# ArduinoUnoQ.net
KiCad netlist of a schematic drawn in Altium Designer
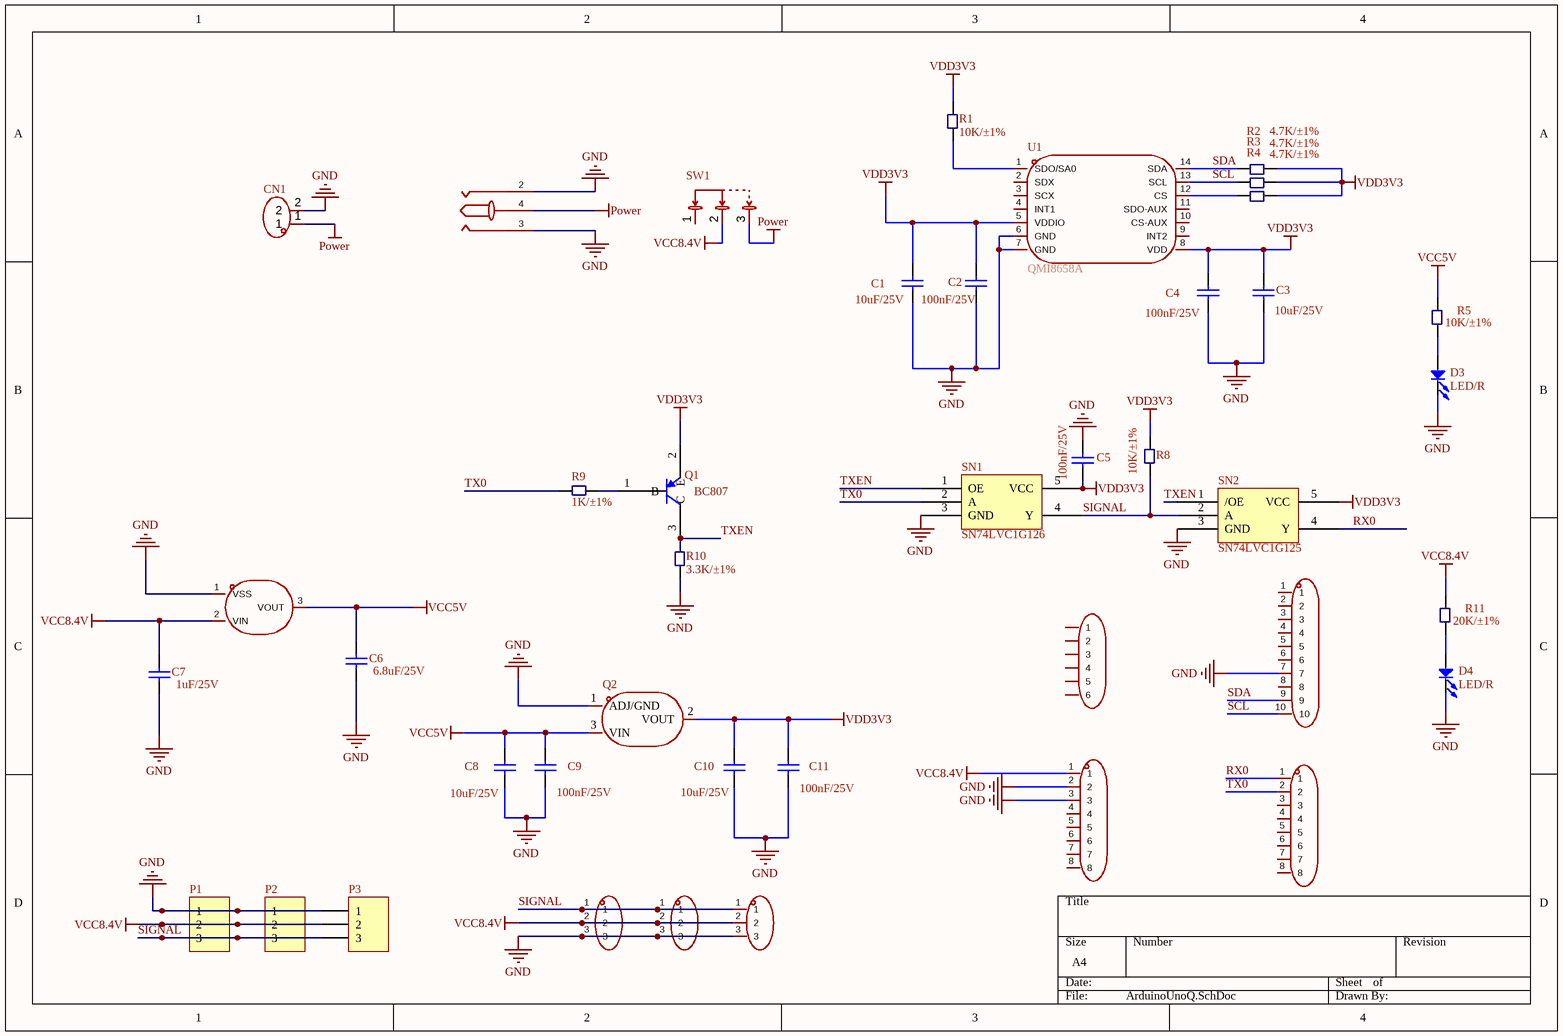
[diagram p0: ArduinoUnoQ.SchDoc]

(export (version "E")
  (design (tool "Eeschema 10.0.6"))
  (components
    (comp (ref "C1")
      (value "10uF/25V")
      (footprint "C0603")
      (description "0603贴片电容，±10%，50V")
      (fields (field (name "PUBLISHER") "Altium Limited"))
      (libsource (lib "ArduinoUnoQ") (part "0603 C"))
    )
    (comp (ref "C2")
      (value "100nF/25V")
      (footprint "C0603")
      (description "0603贴片电容，±10%，50V")
      (fields (field (name "PUBLISHER") "Altium Limited"))
      (libsource (lib "ArduinoUnoQ") (part "0603 C"))
    )
    (comp (ref "C3")
      (value "10uF/25V")
      (footprint "C0603")
      (description "0603贴片电容，±10%，50V")
      (fields (field (name "PUBLISHER") "Altium Limited"))
      (libsource (lib "ArduinoUnoQ") (part "0603 C"))
    )
    (comp (ref "C4")
      (value "100nF/25V")
      (footprint "C0603")
      (description "0603贴片电容，±10%，50V")
      (fields (field (name "PUBLISHER") "Altium Limited"))
      (libsource (lib "ArduinoUnoQ") (part "0603 C"))
    )
    (comp (ref "C5")
      (value "100nF/25V")
      (footprint "C0603")
      (description "0603贴片电容，±10%，50V")
      (libsource (lib "Cap") (part "0603 10nF (103) 10% 50V"))
    )
    (comp (ref "C6")
      (value "6.8uF/25V")
      (footprint "C0603")
      (description "0603贴片电容，±10%，50V")
      (fields (field (name "PUBLISHER") "Altium Limited"))
      (libsource (lib "ArduinoUnoQ") (part "0603 C"))
    )
    (comp (ref "C7")
      (value "1uF/25V")
      (footprint "C0603")
      (description "0603贴片电容，±10%，50V")
      (fields (field (name "PUBLISHER") "Altium Limited"))
      (libsource (lib "ArduinoUnoQ") (part "0603 C"))
    )
    (comp (ref "C8")
      (value "10uF/25V")
      (footprint "C0603")
      (description "0603贴片电容，±10%，50V")
      (fields (field (name "PUBLISHER") "Altium Limited"))
      (libsource (lib "ArduinoUnoQ") (part "0603 C"))
    )
    (comp (ref "C9")
      (value "100nF/25V")
      (footprint "C0603")
      (description "0603贴片电容，±10%，50V")
      (fields (field (name "PUBLISHER") "Altium Limited"))
      (libsource (lib "ArduinoUnoQ") (part "0603 C"))
    )
    (comp (ref "C10")
      (value "10uF/25V")
      (footprint "C0603")
      (description "0603贴片电容，±10%，50V")
      (fields (field (name "PUBLISHER") "Altium Limited"))
      (libsource (lib "ArduinoUnoQ") (part "0603 C"))
    )
    (comp (ref "C11")
      (value "100nF/25V")
      (footprint "C0603")
      (description "0603贴片电容，±10%，50V")
      (fields (field (name "PUBLISHER") "Altium Limited"))
      (libsource (lib "ArduinoUnoQ") (part "0603 C"))
    )
    (comp (ref "CN1")
      (value "ZX-XH2.54-2PWZ")
      (footprint "CONN-TH_2P-P2.50_ZX-XH2.54-2PWZ")
      (fields (field (name "MANUFACTURER") "Megastar(兆星)"))
      (libsource (lib "ArduinoUnoQ") (part "ZX-XH2.54-2PWZ"))
    )
    (comp (ref "D3")
      (value "LED/R")
      (footprint "D_SOD_523")
      (description "Typical INFRARED GaAs LED")
      (fields (field (name "PUBLISHER") "Altium Limited"))
      (libsource (lib "luwu") (part "LED"))
    )
    (comp (ref "D4")
      (value "LED/R")
      (footprint "D_SOD_523")
      (description "Typical INFRARED GaAs LED")
      (fields (field (name "PUBLISHER") "Altium Limited"))
      (libsource (lib "ArduinoUnoQ") (part "LED"))
    )
    (comp (ref "DC1")
      (value "kh-dc-007b-2.1g")
      (footprint "DC-IN-TH_KH-DC-007B-2.1G")
      (description "连接器类型:DC电源插座;安装方式:弯插;触点内径:-;触点外径:-;额定电流:3A;额定电压:50V;工作温度:-30℃~+70℃;")
      (fields
        (field (name "MANUFACTURER") "kinghelm(金航标)")
        (field (name "MANUFACTURERPART") "KH-DC-007B-2.1G")
      )
      (libsource (lib "ArduinoUnoQ") (part "kh-dc-007b-2.1g"))
    )
    (comp (ref "H1")
      (value "pz254v-11-06p")
      (footprint "HDR-TH_6P-P2.54-V-M-1")
      (fields (field (name "MANUFACTURER") "BOOMELE(博穆精密)") (field (name "MANUFACTURERPART") "2.54-1x6P直针"))
      (libsource (lib "ArduinoUnoQ") (part "pz254v-11-06p"))
    )
    (comp (ref "H2")
      (value "pz254v-11-10p")
      (footprint "HDR-TH_10P-P2.54-V-M")
      (fields (field (name "MANUFACTURER") "XFCN(兴飞)") (field (name "MANUFACTURERPART") "PZ254V-11-10P"))
      (libsource (lib "ArduinoUnoQ") (part "pz254v-11-10p"))
    )
    (comp (ref "H3")
      (value "pz254v-11-08p")
      (footprint "HDR-TH_8P-P2.54-V-M")
      (fields (field (name "MANUFACTURER") "XFCN(兴飞)") (field (name "MANUFACTURERPART") "PZ254V-11-08P"))
      (libsource (lib "ArduinoUnoQ") (part "pz254v-11-08p"))
    )
    (comp (ref "H4")
      (value "pz254v-11-08p")
      (footprint "HDR-TH_8P-P2.54-V-M")
      (fields (field (name "MANUFACTURER") "XFCN(兴飞)") (field (name "MANUFACTURERPART") "PZ254V-11-08P"))
      (libsource (lib "ArduinoUnoQ") (part "pz254v-11-08p"))
    )
    (comp (ref "P1")
      (value "mx1.25 1*3P")
      (footprint "MX 1.25-WI-3P")
      (description "1x3P 间距:1.25mm 直插")
      (fields (field (name "PUBLISHER") "Altium Limited"))
      (libsource (lib "Miscellaneous Connectors") (part "Header 3"))
    )
    (comp (ref "P2")
      (value "mx1.25 1*3P")
      (footprint "MX 1.25-WI-3P")
      (description "1x3P 间距:1.25mm 直插")
      (fields (field (name "PUBLISHER") "Altium Limited"))
      (libsource (lib "Miscellaneous Connectors") (part "Header 3"))
    )
    (comp (ref "P3")
      (value "mx1.25 1*3P")
      (footprint "MX 1.25-WI-3P")
      (description "1x3P 间距:1.25mm 直插")
      (fields (field (name "PUBLISHER") "Altium Limited"))
      (libsource (lib "ArduinoUnoQ") (part "Header 3"))
    )
    (comp (ref "Q1")
      (value "BC807")
      (footprint "SOT-23-3")
      (description "hfe=250~600 PNP 电流:500mA 电压:45V")
      (fields (field (name "PUBLISHER") "Altium Limited"))
      (libsource (lib "XGOMINI_V2") (part "PNP 60V 600mA"))
    )
    (comp (ref "Q2")
      (value "AMS1117-3.3V")
      (footprint "SOT-89-3_L4.5-W2.5-P1.50-LS4.2-BR")
      (description "输入18V 输出3.3V 1A，SOT-89封装")
      (fields (field (name "MANUFACTURER") "MSKSEMI(美森科)"))
      (libsource (lib "ArduinoUnoQ") (part "AMS1117-3.3V_SOT89"))
    )
    (comp (ref "R1")
      (value "10K/±1%")
      (footprint "R0603")
      (description "厚膜电阻  ±1% 100mW")
      (fields (field (name "PUBLISHER") "Altium Limited"))
      (libsource (lib "ArduinoUnoQ") (part "Res2_1"))
    )
    (comp (ref "R2")
      (value "4.7K/±1%")
      (footprint "R0603")
      (description "厚膜电阻  ±1% 100mW")
      (fields (field (name "PUBLISHER") "Altium Limited"))
      (libsource (lib "ArduinoUnoQ") (part "Res2_1"))
    )
    (comp (ref "R3")
      (value "4.7K/±1%")
      (footprint "R0603")
      (description "厚膜电阻  ±1% 100mW")
      (fields (field (name "PUBLISHER") "Altium Limited"))
      (libsource (lib "ArduinoUnoQ") (part "Res2_1"))
    )
    (comp (ref "R4")
      (value "4.7K/±1%")
      (footprint "R0603")
      (description "厚膜电阻  ±1% 100mW")
      (fields (field (name "PUBLISHER") "Altium Limited"))
      (libsource (lib "ArduinoUnoQ") (part "Res2_1"))
    )
    (comp (ref "R5")
      (value "10K/±1%")
      (footprint "R0603")
      (description "厚膜电阻  ±1% 100mW")
      (fields (field (name "PUBLISHER") "Altium Limited"))
      (libsource (lib "ArduinoUnoQ") (part "Res2_1"))
    )
    (comp (ref "R8")
      (value "10K/±1%")
      (footprint "R0603")
      (description "厚膜电阻  ±1% 100mW")
      (fields (field (name "PUBLISHER") "Altium Limited"))
      (libsource (lib "ArduinoUnoQ") (part "Res2_1"))
    )
    (comp (ref "R9")
      (value "1K/±1%")
      (footprint "R0603")
      (description "厚膜电阻 ±1% 100mW")
      (fields (field (name "PUBLISHER") "Altium Limited"))
      (libsource (lib "ArduinoUnoQ") (part "Res2_1"))
    )
    (comp (ref "R10")
      (value "3.3K/±1%")
      (footprint "R0603")
      (description "厚膜电阻  ±1% 100mW")
      (fields (field (name "PUBLISHER") "Altium Limited"))
      (libsource (lib "ArduinoUnoQ") (part "Res2_1"))
    )
    (comp (ref "R11")
      (value "20K/±1%")
      (footprint "R0603")
      (description "厚膜电阻  ±1% 100mW")
      (fields (field (name "PUBLISHER") "Altium Limited"))
      (libsource (lib "ArduinoUnoQ") (part "Res2_1"))
    )
    (comp (ref "SN1")
      (value "SN74LVC1G126")
      (footprint "SOT_23_5")
      (description "三态输出，单路总线缓冲门")
      (libsource (lib "XGOLITE_V2") (part "SN74LVC1G126"))
    )
    (comp (ref "SN2")
      (value "SN74LVC1G125")
      (footprint "SOT_23_5")
      (description "单总线缓冲门，带三态输出")
      (libsource (lib "XDOG") (part "SN74LVC1G125"))
    )
    (comp (ref "SW1")
      (value "SS-12D06L5")
      (footprint "SW-TH_3P-P4.70_L11.1-W12.7")
      (description "电路结构:单刀双掷;安装方式:-;开关颜色:黑色;额定电流:3A;额定电压:125V;工作寿命:1万次;")
      (fields (field (name "MANUFACTURER") "XKB Connection(中国星坤)"))
      (libsource (lib "ArduinoUnoQ") (part "SS-12D06L5"))
    )
    (comp (ref "U1")
      (value "QMI8658A")
      (footprint "LGA-14_L3.0-W2.5-P0.50-TL")
      (description "六轴陀螺仪  陀螺仪量程(MAX) ±2048dps  加速度计量程(MAX) ±16g")
      (libsource (lib "ArduinoUnoQ") (part "QMI8658A"))
    )
    (comp (ref "U2")
      (value "h7651-50pr")
      (footprint "SOT-89-3_L4.5-W2.5-P1.50-LS4.2-BR")
      (description "输出极性:正极;工作电压:8.5V;输出电压:5V;输出电流:1A;电源纹波抑制比(PSRR):-;输出类型:固定;")
      (fields (field (name "MANUFACTURER") "Siproin(上海矽朋)") (field (name "MANUFACTURERPART") "H7651-50PR"))
      (libsource (lib "ArduinoUnoQ") (part "h7651-50pr"))
    )
    (comp (ref "U3")
      (value "292253-3")
      (footprint "CONN-TH_3P-P2.00_TE_292253-3")
      (description "插针结构:1x3P;间距:2mm;安装方式:弯插;总PIN数:3P;排数:1;每排PIN数:3;额定电流:4A;触头材质:黄铜;触头镀层:锡;工作温度:-40℃~+105℃;")
      (fields (field (name "MANUFACTURER") "TE Connectivity(泰科电子)"))
      (libsource (lib "ArduinoUnoQ") (part "292253-3"))
    )
    (comp (ref "U4")
      (value "292253-3")
      (footprint "CONN-TH_3P-P2.00_TE_292253-3")
      (description "插针结构:1x3P;间距:2mm;安装方式:弯插;总PIN数:3P;排数:1;每排PIN数:3;额定电流:4A;触头材质:黄铜;触头镀层:锡;工作温度:-40℃~+105℃;")
      (fields (field (name "MANUFACTURER") "TE Connectivity(泰科电子)"))
      (libsource (lib "ArduinoUnoQ") (part "292253-3"))
    )
    (comp (ref "U5")
      (value "292253-3")
      (footprint "CONN-TH_3P-P2.00_TE_292253-3")
      (description "插针结构:1x3P;间距:2mm;安装方式:弯插;总PIN数:3P;排数:1;每排PIN数:3;额定电流:4A;触头材质:黄铜;触头镀层:锡;工作温度:-40℃~+105℃;")
      (fields (field (name "MANUFACTURER") "TE Connectivity(泰科电子)"))
      (libsource (lib "ArduinoUnoQ") (part "292253-3"))
    )
  )
  (nets
    (net (code "1") (name "/RX0") (class "Default")
      (node (ref "H4") (pin "1") (pinfunction "1_1") (pintype "passive"))
      (node (ref "SN2") (pin "4") (pinfunction "Y_4") (pintype "passive"))
    )
    (net (code "2") (name "/SCL") (class "Default")
      (node (ref "H2") (pin "10") (pinfunction "10_10") (pintype "passive"))
      (node (ref "R3") (pin "1") (pinfunction "1_1") (pintype "passive"))
      (node (ref "U1") (pin "13") (pinfunction "SCL_13") (pintype "passive"))
    )
    (net (code "3") (name "/SDA") (class "Default")
      (node (ref "H2") (pin "9") (pinfunction "9_9") (pintype "passive"))
      (node (ref "R2") (pin "1") (pinfunction "1_1") (pintype "passive"))
      (node (ref "U1") (pin "14") (pinfunction "SDA_14") (pintype "passive"))
    )
    (net (code "4") (name "/SIGNAL") (class "Default")
      (node (ref "P1") (pin "3") (pinfunction "3_3") (pintype "passive"))
      (node (ref "P2") (pin "3") (pinfunction "3_3") (pintype "passive"))
      (node (ref "P3") (pin "3") (pinfunction "3_3") (pintype "passive"))
      (node (ref "R8") (pin "2") (pinfunction "2_2") (pintype "passive"))
      (node (ref "SN1") (pin "4") (pinfunction "Y_4") (pintype "passive"))
      (node (ref "SN2") (pin "2") (pinfunction "A_2") (pintype "passive"))
      (node (ref "U3") (pin "1") (pinfunction "1_1") (pintype "passive"))
      (node (ref "U4") (pin "1") (pinfunction "1_1") (pintype "passive"))
      (node (ref "U5") (pin "1") (pinfunction "1_1") (pintype "passive"))
    )
    (net (code "5") (name "/TX0") (class "Default")
      (node (ref "H4") (pin "2") (pinfunction "2_2") (pintype "passive"))
      (node (ref "R9") (pin "2") (pinfunction "2_2") (pintype "passive"))
      (node (ref "SN1") (pin "2") (pinfunction "A_2") (pintype "passive"))
    )
    (net (code "6") (name "/TXEN") (class "Default")
      (node (ref "Q1") (pin "3") (pinfunction "C_3") (pintype "passive"))
      (node (ref "R10") (pin "1") (pinfunction "1_1") (pintype "passive"))
      (node (ref "SN1") (pin "1") (pinfunction "OE_1") (pintype "passive"))
      (node (ref "SN2") (pin "1") (pinfunction "/OE_1") (pintype "passive"))
    )
    (net (code "7") (name "GND") (class "Default")
      (node (ref "C1") (pin "1") (pinfunction "1_1") (pintype "passive"))
      (node (ref "C10") (pin "1") (pinfunction "1_1") (pintype "passive"))
      (node (ref "C11") (pin "1") (pinfunction "1_1") (pintype "passive"))
      (node (ref "C2") (pin "1") (pinfunction "1_1") (pintype "passive"))
      (node (ref "C3") (pin "1") (pinfunction "1_1") (pintype "passive"))
      (node (ref "C4") (pin "1") (pinfunction "1_1") (pintype "passive"))
      (node (ref "C5") (pin "2") (pinfunction "2_2") (pintype "passive"))
      (node (ref "C6") (pin "1") (pinfunction "1_1") (pintype "passive"))
      (node (ref "C7") (pin "1") (pinfunction "1_1") (pintype "passive"))
      (node (ref "C8") (pin "1") (pinfunction "1_1") (pintype "passive"))
      (node (ref "C9") (pin "1") (pinfunction "1_1") (pintype "passive"))
      (node (ref "CN1") (pin "2") (pinfunction "2_2") (pintype "passive"))
      (node (ref "D3") (pin "2") (pinfunction "K_2") (pintype "passive"))
      (node (ref "D4") (pin "2") (pinfunction "K_2") (pintype "passive"))
      (node (ref "DC1") (pin "2") (pinfunction "2_2") (pintype "passive"))
      (node (ref "DC1") (pin "3") (pinfunction "3_3") (pintype "passive"))
      (node (ref "H2") (pin "7") (pinfunction "7_7") (pintype "passive"))
      (node (ref "H3") (pin "2") (pinfunction "2_2") (pintype "passive"))
      (node (ref "H3") (pin "3") (pinfunction "3_3") (pintype "passive"))
      (node (ref "P1") (pin "1") (pinfunction "1_1") (pintype "passive"))
      (node (ref "P2") (pin "1") (pinfunction "1_1") (pintype "passive"))
      (node (ref "P3") (pin "1") (pinfunction "1_1") (pintype "passive"))
      (node (ref "Q2") (pin "1") (pinfunction "ADJ/GND_1") (pintype "passive"))
      (node (ref "R10") (pin "2") (pinfunction "2_2") (pintype "passive"))
      (node (ref "SN1") (pin "3") (pinfunction "GND_3") (pintype "passive"))
      (node (ref "SN2") (pin "3") (pinfunction "GND_3") (pintype "passive"))
      (node (ref "U1") (pin "6") (pinfunction "GND_6") (pintype "passive"))
      (node (ref "U1") (pin "7") (pinfunction "GND_7") (pintype "passive"))
      (node (ref "U2") (pin "1") (pinfunction "VSS_1") (pintype "passive"))
      (node (ref "U3") (pin "3") (pinfunction "3_3") (pintype "passive"))
      (node (ref "U4") (pin "3") (pinfunction "3_3") (pintype "passive"))
      (node (ref "U5") (pin "3") (pinfunction "3_3") (pintype "passive"))
    )
    (net (code "8") (name "Net-(D3-A)") (class "Default")
      (node (ref "D3") (pin "1") (pinfunction "A_1") (pintype "passive"))
      (node (ref "R5") (pin "2") (pinfunction "2_2") (pintype "passive"))
    )
    (net (code "9") (name "Net-(D4-A)") (class "Default")
      (node (ref "D4") (pin "1") (pinfunction "A_1") (pintype "passive"))
      (node (ref "R11") (pin "2") (pinfunction "2_2") (pintype "passive"))
    )
    (net (code "10") (name "Net-(Q1-B)") (class "Default")
      (node (ref "Q1") (pin "1") (pinfunction "B_1") (pintype "passive"))
      (node (ref "R9") (pin "1") (pinfunction "1_1") (pintype "passive"))
    )
    (net (code "11") (name "Net-(U1-CS)") (class "Default")
      (node (ref "R4") (pin "1") (pinfunction "1_1") (pintype "passive"))
      (node (ref "U1") (pin "12") (pinfunction "CS_12") (pintype "passive"))
    )
    (net (code "12") (name "Net-(U1-SDO{slash}SA0)") (class "Default")
      (node (ref "R1") (pin "2") (pinfunction "2_2") (pintype "passive"))
      (node (ref "U1") (pin "1") (pinfunction "SDO/SA0_1") (pintype "passive"))
    )
    (net (code "13") (name "Power") (class "Default")
      (node (ref "CN1") (pin "1") (pinfunction "1_1") (pintype "passive"))
      (node (ref "DC1") (pin "4") (pinfunction "4_4") (pintype "passive"))
      (node (ref "SW1") (pin "3") (pinfunction "3_3") (pintype "passive"))
    )
    (net (code "14") (name "VCC5V") (class "Default")
      (node (ref "C6") (pin "2") (pinfunction "2_2") (pintype "passive"))
      (node (ref "C8") (pin "2") (pinfunction "2_2") (pintype "passive"))
      (node (ref "C9") (pin "2") (pinfunction "2_2") (pintype "passive"))
      (node (ref "Q2") (pin "3") (pinfunction "VIN_3") (pintype "passive"))
      (node (ref "R5") (pin "1") (pinfunction "1_1") (pintype "passive"))
      (node (ref "U2") (pin "3") (pinfunction "VOUT_3") (pintype "passive"))
    )
    (net (code "15") (name "VCC8.4V") (class "Default")
      (node (ref "C7") (pin "2") (pinfunction "2_2") (pintype "passive"))
      (node (ref "H3") (pin "1") (pinfunction "1_1") (pintype "passive"))
      (node (ref "P1") (pin "2") (pinfunction "2_2") (pintype "passive"))
      (node (ref "P2") (pin "2") (pinfunction "2_2") (pintype "passive"))
      (node (ref "P3") (pin "2") (pinfunction "2_2") (pintype "passive"))
      (node (ref "R11") (pin "1") (pinfunction "1_1") (pintype "passive"))
      (node (ref "SW1") (pin "2") (pinfunction "2_2") (pintype "passive"))
      (node (ref "U2") (pin "2") (pinfunction "VIN_2") (pintype "passive"))
      (node (ref "U3") (pin "2") (pinfunction "2_2") (pintype "passive"))
      (node (ref "U4") (pin "2") (pinfunction "2_2") (pintype "passive"))
      (node (ref "U5") (pin "2") (pinfunction "2_2") (pintype "passive"))
    )
    (net (code "16") (name "VDD3V3") (class "Default")
      (node (ref "C1") (pin "2") (pinfunction "2_2") (pintype "passive"))
      (node (ref "C10") (pin "2") (pinfunction "2_2") (pintype "passive"))
      (node (ref "C11") (pin "2") (pinfunction "2_2") (pintype "passive"))
      (node (ref "C2") (pin "2") (pinfunction "2_2") (pintype "passive"))
      (node (ref "C3") (pin "2") (pinfunction "2_2") (pintype "passive"))
      (node (ref "C4") (pin "2") (pinfunction "2_2") (pintype "passive"))
      (node (ref "C5") (pin "1") (pinfunction "1_1") (pintype "passive"))
      (node (ref "Q1") (pin "2") (pinfunction "E_2") (pintype "passive"))
      (node (ref "Q2") (pin "2") (pinfunction "VOUT_2") (pintype "passive"))
      (node (ref "R1") (pin "1") (pinfunction "1_1") (pintype "passive"))
      (node (ref "R2") (pin "2") (pinfunction "2_2") (pintype "passive"))
      (node (ref "R3") (pin "2") (pinfunction "2_2") (pintype "passive"))
      (node (ref "R4") (pin "2") (pinfunction "2_2") (pintype "passive"))
      (node (ref "R8") (pin "1") (pinfunction "1_1") (pintype "passive"))
      (node (ref "SN1") (pin "5") (pinfunction "VCC_5") (pintype "passive"))
      (node (ref "SN2") (pin "5") (pinfunction "VCC_5") (pintype "passive"))
      (node (ref "U1") (pin "5") (pinfunction "VDDIO_5") (pintype "passive"))
      (node (ref "U1") (pin "8") (pinfunction "VDD_8") (pintype "passive"))
    )
    (net (code "17") (name "unconnected-(H1-Pad1)") (class "Default")
      (node (ref "H1") (pin "1") (pinfunction "1_1") (pintype "passive"))
    )
    (net (code "18") (name "unconnected-(H1-Pad2)") (class "Default")
      (node (ref "H1") (pin "2") (pinfunction "2_2") (pintype "passive"))
    )
    (net (code "19") (name "unconnected-(H1-Pad3)") (class "Default")
      (node (ref "H1") (pin "3") (pinfunction "3_3") (pintype "passive"))
    )
    (net (code "20") (name "unconnected-(H1-Pad4)") (class "Default")
      (node (ref "H1") (pin "4") (pinfunction "4_4") (pintype "passive"))
    )
    (net (code "21") (name "unconnected-(H1-Pad5)") (class "Default")
      (node (ref "H1") (pin "5") (pinfunction "5_5") (pintype "passive"))
    )
    (net (code "22") (name "unconnected-(H1-Pad6)") (class "Default")
      (node (ref "H1") (pin "6") (pinfunction "6_6") (pintype "passive"))
    )
    (net (code "23") (name "unconnected-(H2-Pad1)") (class "Default")
      (node (ref "H2") (pin "1") (pinfunction "1_1") (pintype "passive"))
    )
    (net (code "24") (name "unconnected-(H2-Pad2)") (class "Default")
      (node (ref "H2") (pin "2") (pinfunction "2_2") (pintype "passive"))
    )
    (net (code "25") (name "unconnected-(H2-Pad3)") (class "Default")
      (node (ref "H2") (pin "3") (pinfunction "3_3") (pintype "passive"))
    )
    (net (code "26") (name "unconnected-(H2-Pad4)") (class "Default")
      (node (ref "H2") (pin "4") (pinfunction "4_4") (pintype "passive"))
    )
    (net (code "27") (name "unconnected-(H2-Pad5)") (class "Default")
      (node (ref "H2") (pin "5") (pinfunction "5_5") (pintype "passive"))
    )
    (net (code "28") (name "unconnected-(H2-Pad6)") (class "Default")
      (node (ref "H2") (pin "6") (pinfunction "6_6") (pintype "passive"))
    )
    (net (code "29") (name "unconnected-(H2-Pad8)") (class "Default")
      (node (ref "H2") (pin "8") (pinfunction "8_8") (pintype "passive"))
    )
    (net (code "30") (name "unconnected-(H3-Pad4)") (class "Default")
      (node (ref "H3") (pin "4") (pinfunction "4_4") (pintype "passive"))
    )
    (net (code "31") (name "unconnected-(H3-Pad5)") (class "Default")
      (node (ref "H3") (pin "5") (pinfunction "5_5") (pintype "passive"))
    )
    (net (code "32") (name "unconnected-(H3-Pad6)") (class "Default")
      (node (ref "H3") (pin "6") (pinfunction "6_6") (pintype "passive"))
    )
    (net (code "33") (name "unconnected-(H3-Pad7)") (class "Default")
      (node (ref "H3") (pin "7") (pinfunction "7_7") (pintype "passive"))
    )
    (net (code "34") (name "unconnected-(H3-Pad8)") (class "Default")
      (node (ref "H3") (pin "8") (pinfunction "8_8") (pintype "passive"))
    )
    (net (code "35") (name "unconnected-(H4-Pad3)") (class "Default")
      (node (ref "H4") (pin "3") (pinfunction "3_3") (pintype "passive"))
    )
    (net (code "36") (name "unconnected-(H4-Pad4)") (class "Default")
      (node (ref "H4") (pin "4") (pinfunction "4_4") (pintype "passive"))
    )
    (net (code "37") (name "unconnected-(H4-Pad5)") (class "Default")
      (node (ref "H4") (pin "5") (pinfunction "5_5") (pintype "passive"))
    )
    (net (code "38") (name "unconnected-(H4-Pad6)") (class "Default")
      (node (ref "H4") (pin "6") (pinfunction "6_6") (pintype "passive"))
    )
    (net (code "39") (name "unconnected-(H4-Pad7)") (class "Default")
      (node (ref "H4") (pin "7") (pinfunction "7_7") (pintype "passive"))
    )
    (net (code "40") (name "unconnected-(H4-Pad8)") (class "Default")
      (node (ref "H4") (pin "8") (pinfunction "8_8") (pintype "passive"))
    )
    (net (code "41") (name "unconnected-(SW1-Pad1)") (class "Default")
      (node (ref "SW1") (pin "1") (pinfunction "1_1") (pintype "passive"))
    )
    (net (code "42") (name "unconnected-(U1-CS-AUX-Pad10)") (class "Default")
      (node (ref "U1") (pin "10") (pinfunction "CS-AUX_10") (pintype "passive"))
    )
    (net (code "43") (name "unconnected-(U1-INT1-Pad4)") (class "Default")
      (node (ref "U1") (pin "4") (pinfunction "INT1_4") (pintype "passive"))
    )
    (net (code "44") (name "unconnected-(U1-INT2-Pad9)") (class "Default")
      (node (ref "U1") (pin "9") (pinfunction "INT2_9") (pintype "passive"))
    )
    (net (code "45") (name "unconnected-(U1-SCX-Pad3)") (class "Default")
      (node (ref "U1") (pin "3") (pinfunction "SCX_3") (pintype "passive"))
    )
    (net (code "46") (name "unconnected-(U1-SDO-AUX-Pad11)") (class "Default")
      (node (ref "U1") (pin "11") (pinfunction "SDO-AUX_11") (pintype "passive"))
    )
    (net (code "47") (name "unconnected-(U1-SDX-Pad2)") (class "Default")
      (node (ref "U1") (pin "2") (pinfunction "SDX_2") (pintype "passive"))
    )
  )
)
